# 10-RF_WIFI.net
KiCad netlist of a schematic drawn in Altium Designer
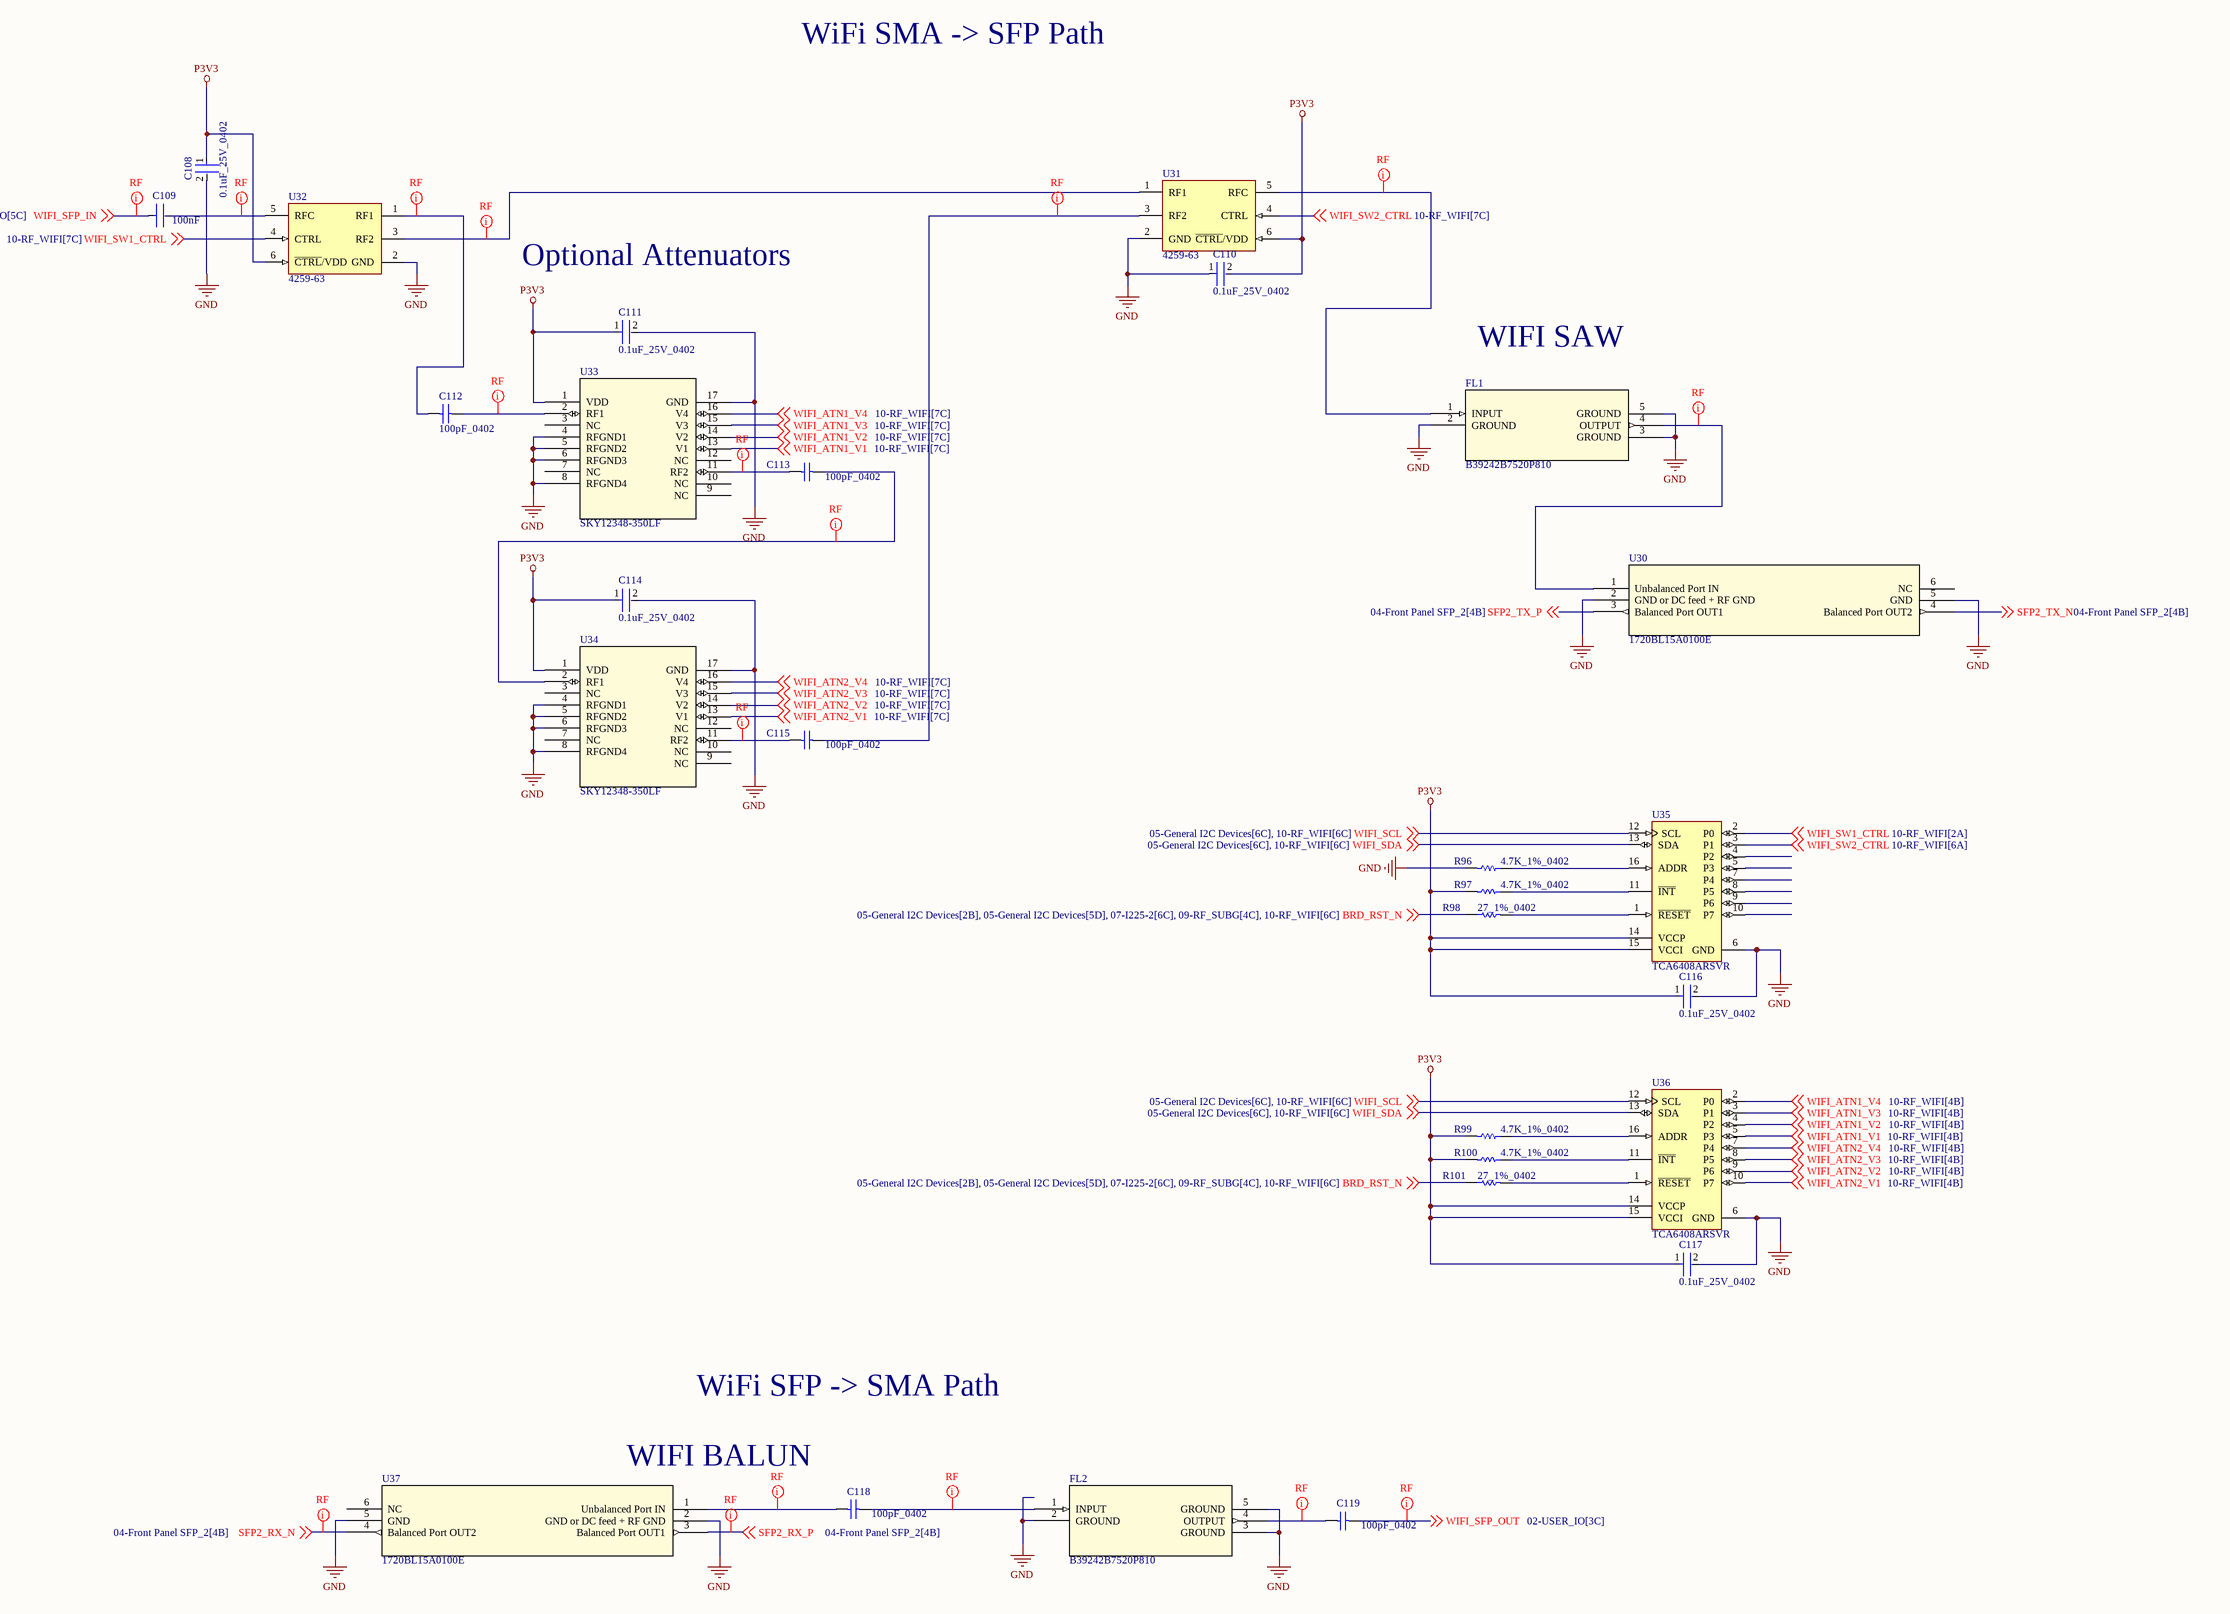
[diagram p0: 10-RF_WIFI.SchDoc]

(export (version "E")
  (design (tool "Eeschema 10.0.6"))
  (components
    (comp (ref "C108")
      (value "0.1uF_25V_0402")
      (footprint "FP-0402-L_1_0_1-W_0_5_0_1-IPC_C")
      (description "General Purpose Ceramic Capacitor, 0402, 100nF, 10%, X7R, 15%, 25V")
      (fields (field (name "VOLTAGE") "25V") (field (name "TOLERANCE") "10%"))
      (libsource (lib "Altium Content Vault") (part "b4654b650e69147ec39a6b967a45e02"))
    )
    (comp (ref "C109")
      (value "100nF")
      (footprint "FP-0402-L_1_0_0_05-W_0_5-IPC_B")
      (description "None")
      (fields (field (name "TOLERANCE") "10%"))
      (libsource (lib "") (part "b4654b650e69147ec39a6b967a45e02_1"))
    )
    (comp (ref "C110")
      (value "0.1uF_25V_0402")
      (footprint "FP-0402-L_1_0_1-W_0_5_0_1-IPC_C")
      (description "General Purpose Ceramic Capacitor, 0402, 100nF, 10%, X7R, 15%, 25V")
      (fields (field (name "VOLTAGE") "25V") (field (name "TOLERANCE") "10%"))
      (libsource (lib "Altium Content Vault") (part "b4654b650e69147ec39a6b967a45e02"))
    )
    (comp (ref "C111")
      (value "0.1uF_25V_0402")
      (footprint "FP-0402-L_1_0_1-W_0_5_0_1-IPC_C")
      (description "General Purpose Ceramic Capacitor, 0402, 100nF, 10%, X7R, 15%, 25V")
      (fields (field (name "VOLTAGE") "25V") (field (name "TOLERANCE") "10%"))
      (libsource (lib "Altium Content Vault") (part "b4654b650e69147ec39a6b967a45e02"))
    )
    (comp (ref "C112")
      (value "100pF_0402")
      (footprint "CAPC1005X55X25ML05T10")
      (fields (field (name "MANUFACTURER") "Murata") (field (name "PART NUMBER") "GRM1555C1H101JA01D"))
      (libsource (lib "Altium Content Vault") (part "CAP"))
    )
    (comp (ref "C113")
      (value "100pF_0402")
      (footprint "CAPC1005X55X25ML05T10")
      (fields (field (name "MANUFACTURER") "Murata") (field (name "PART NUMBER") "GRM1555C1H101JA01D"))
      (libsource (lib "Altium Content Vault") (part "CAP"))
    )
    (comp (ref "C114")
      (value "0.1uF_25V_0402")
      (footprint "FP-0402-L_1_0_1-W_0_5_0_1-IPC_C")
      (description "General Purpose Ceramic Capacitor, 0402, 100nF, 10%, X7R, 15%, 25V")
      (fields (field (name "VOLTAGE") "25V") (field (name "TOLERANCE") "10%"))
      (libsource (lib "Altium Content Vault") (part "b4654b650e69147ec39a6b967a45e02"))
    )
    (comp (ref "C115")
      (value "100pF_0402")
      (footprint "CAPC1005X55X25ML05T10")
      (fields (field (name "MANUFACTURER") "Murata") (field (name "PART NUMBER") "GRM1555C1H101JA01D"))
      (libsource (lib "Altium Content Vault") (part "CAP"))
    )
    (comp (ref "C116")
      (value "0.1uF_25V_0402")
      (footprint "FP-0402-L_1_0_1-W_0_5_0_1-IPC_C")
      (description "General Purpose Ceramic Capacitor, 0402, 100nF, 10%, X7R, 15%, 25V")
      (fields (field (name "VOLTAGE") "25V") (field (name "TOLERANCE") "10%"))
      (libsource (lib "Altium Content Vault") (part "b4654b650e69147ec39a6b967a45e02"))
    )
    (comp (ref "C117")
      (value "0.1uF_25V_0402")
      (footprint "FP-0402-L_1_0_1-W_0_5_0_1-IPC_C")
      (description "General Purpose Ceramic Capacitor, 0402, 100nF, 10%, X7R, 15%, 25V")
      (fields (field (name "VOLTAGE") "25V") (field (name "TOLERANCE") "10%"))
      (libsource (lib "Altium Content Vault") (part "b4654b650e69147ec39a6b967a45e02"))
    )
    (comp (ref "C118")
      (value "100pF_0402")
      (footprint "CAPC1005X55X25ML05T10")
      (fields (field (name "MANUFACTURER") "Murata") (field (name "PART NUMBER") "GRM1555C1H101JA01D"))
      (libsource (lib "Altium Content Vault") (part "CAP"))
    )
    (comp (ref "C119")
      (value "100pF_0402")
      (footprint "CAPC1005X55X25ML05T10")
      (fields (field (name "MANUFACTURER") "Murata") (field (name "PART NUMBER") "GRM1555C1H101JA01D"))
      (libsource (lib "Altium Content Vault") (part "CAP"))
    )
    (comp (ref "FL1")
      (value "B39242B7520P810")
      (footprint "SMD5_SAW-B7520_QUA")
      (description "No Description Available")
      (libsource (lib "B39242B7520P810") (part "B39242B7520P810"))
    )
    (comp (ref "FL2")
      (value "B39242B7520P810")
      (footprint "SMD5_SAW-B7520_QUA")
      (description "No Description Available")
      (libsource (lib "B39242B7520P810") (part "B39242B7520P810"))
    )
    (comp (ref "R96")
      (value "4.7K_1%_0402")
      (footprint "RESC1005X40X25NL10T10")
      (fields (field (name "MANUFACTURER") "Bourns") (field (name "PART NUMBER") "CR0402-FX-4701GLF"))
      (libsource (lib "Altium Content Vault") (part "RES"))
    )
    (comp (ref "R97")
      (value "4.7K_1%_0402")
      (footprint "RESC1005X40X25NL10T10")
      (fields (field (name "MANUFACTURER") "Bourns") (field (name "PART NUMBER") "CR0402-FX-4701GLF"))
      (libsource (lib "Altium Content Vault") (part "RES"))
    )
    (comp (ref "R98")
      (value "27_1%_0402")
      (footprint "RESC1005X40X25NL05T05")
      (fields (field (name "PART NUMBER") "CRCW040227R0FKED") (field (name "MANUFACTURER") "Vishay Dale"))
      (libsource (lib "Altium Content Vault") (part "RES"))
    )
    (comp (ref "R99")
      (value "4.7K_1%_0402")
      (footprint "RESC1005X40X25NL10T10")
      (fields (field (name "MANUFACTURER") "Bourns") (field (name "PART NUMBER") "CR0402-FX-4701GLF"))
      (libsource (lib "Altium Content Vault") (part "RES"))
    )
    (comp (ref "R100")
      (value "4.7K_1%_0402")
      (footprint "RESC1005X40X25NL10T10")
      (fields (field (name "MANUFACTURER") "Bourns") (field (name "PART NUMBER") "CR0402-FX-4701GLF"))
      (libsource (lib "Altium Content Vault") (part "RES"))
    )
    (comp (ref "R101")
      (value "27_1%_0402")
      (footprint "RESC1005X40X25NL05T05")
      (fields (field (name "PART NUMBER") "CRCW040227R0FKED") (field (name "MANUFACTURER") "Vishay Dale"))
      (libsource (lib "Altium Content Vault") (part "RES"))
    )
    (comp (ref "U30")
      (value "1720BL15A0100E")
      (footprint "SMT_15B0050E_JOT")
      (description "No Description Available")
      (libsource (lib "") (part "1720BL15A0100E_1"))
    )
    (comp (ref "U31")
      (value "4259-63")
      (footprint "PERE-SC-70-6_M")
      (description "IC RF Switch SPDT, 50 Ohm, 6-Pin SC70, RoHS, Tape and Reel")
      (fields (field (name "MANUFACTURER") "Peregrine Semiconductor"))
      (libsource (lib "") (part "PERE-PE4259-6_1"))
    )
    (comp (ref "U32")
      (value "4259-63")
      (footprint "PERE-SC-70-6_M")
      (description "IC RF Switch SPDT, 50 Ohm, 6-Pin SC70, RoHS, Tape and Reel")
      (fields (field (name "MANUFACTURER") "Peregrine Semiconductor"))
      (libsource (lib "Altium Content Vault") (part "PERE-PE4259-6"))
    )
    (comp (ref "U33")
      (value "SKY12348-350LF")
      (footprint "SKY12348-350LF_SKY")
      (description "No Description Available")
      (libsource (lib "SKY12348-350LF") (part "SKY12348-350LF"))
    )
    (comp (ref "U34")
      (value "SKY12348-350LF")
      (footprint "SKY12348-350LF_SKY")
      (description "No Description Available")
      (libsource (lib "SKY12348-350LF") (part "SKY12348-350LF"))
    )
    (comp (ref "U35")
      (value "TCA6408ARSVR")
      (footprint "RSV0016A_V")
      (fields (field (name "MANUFACTURER") "Texas Instruments"))
      (libsource (lib "Altium Content Vault") (part "TI-TCA6408A-UQFN_RSV-16"))
    )
    (comp (ref "U36")
      (value "TCA6408ARSVR")
      (footprint "RSV0016A_V")
      (fields (field (name "MANUFACTURER") "Texas Instruments"))
      (libsource (lib "Altium Content Vault") (part "TI-TCA6408A-UQFN_RSV-16"))
    )
    (comp (ref "U37")
      (value "1720BL15A0100E")
      (footprint "SMT_15B0050E_JOT")
      (description "No Description Available")
      (libsource (lib "1720BL15A0100E") (part "1720BL15A0100E"))
    )
  )
  (nets
    (net (code "1") (name "BRD_RST_N") (class "Default")
      (node (ref "R101") (pin "1") (pinfunction "1_1") (pintype "passive"))
      (node (ref "R98") (pin "1") (pinfunction "1_1") (pintype "passive"))
    )
    (net (code "2") (name "GND") (class "Default")
      (node (ref "C108") (pin "2") (pinfunction "2_2") (pintype "passive"))
      (node (ref "C110") (pin "1") (pinfunction "1_1") (pintype "passive"))
      (node (ref "C111") (pin "2") (pinfunction "2_2") (pintype "passive"))
      (node (ref "C114") (pin "2") (pinfunction "2_2") (pintype "passive"))
      (node (ref "C116") (pin "2") (pinfunction "2_2") (pintype "passive"))
      (node (ref "C117") (pin "2") (pinfunction "2_2") (pintype "passive"))
      (node (ref "FL1") (pin "2") (pinfunction "GROUND_2") (pintype "power_in"))
      (node (ref "FL1") (pin "3") (pinfunction "GROUND_3") (pintype "power_in"))
      (node (ref "FL1") (pin "5") (pinfunction "GROUND_5") (pintype "power_in"))
      (node (ref "FL2") (pin "2") (pinfunction "GROUND_2") (pintype "power_in"))
      (node (ref "FL2") (pin "3") (pinfunction "GROUND_3") (pintype "power_in"))
      (node (ref "FL2") (pin "5") (pinfunction "GROUND_5") (pintype "power_in"))
      (node (ref "R96") (pin "2") (pinfunction "2_2") (pintype "passive"))
      (node (ref "U30") (pin "2") (pinfunction "GND_or_DC_feed_+_RF_GND_2") (pintype "power_in"))
      (node (ref "U30") (pin "5") (pinfunction "GND_5") (pintype "power_in"))
      (node (ref "U31") (pin "2") (pinfunction "GND_2") (pintype "power_in"))
      (node (ref "U32") (pin "2") (pinfunction "GND_2") (pintype "power_in"))
      (node (ref "U33") (pin "17") (pinfunction "GND_17") (pintype "power_in"))
      (node (ref "U33") (pin "4") (pinfunction "RFGND1_4") (pintype "power_in"))
      (node (ref "U33") (pin "5") (pinfunction "RFGND2_5") (pintype "power_in"))
      (node (ref "U33") (pin "6") (pinfunction "RFGND3_6") (pintype "power_in"))
      (node (ref "U33") (pin "8") (pinfunction "RFGND4_8") (pintype "power_in"))
      (node (ref "U34") (pin "17") (pinfunction "GND_17") (pintype "power_in"))
      (node (ref "U34") (pin "4") (pinfunction "RFGND1_4") (pintype "power_in"))
      (node (ref "U34") (pin "5") (pinfunction "RFGND2_5") (pintype "power_in"))
      (node (ref "U34") (pin "6") (pinfunction "RFGND3_6") (pintype "power_in"))
      (node (ref "U34") (pin "8") (pinfunction "RFGND4_8") (pintype "power_in"))
      (node (ref "U35") (pin "6") (pinfunction "GND_6") (pintype "power_in"))
      (node (ref "U36") (pin "6") (pinfunction "GND_6") (pintype "power_in"))
      (node (ref "U37") (pin "2") (pinfunction "GND_or_DC_feed_+_RF_GND_2") (pintype "power_in"))
      (node (ref "U37") (pin "5") (pinfunction "GND_5") (pintype "power_in"))
    )
    (net (code "3") (name "Net-(FL1-INPUT)") (class "Default")
      (node (ref "FL1") (pin "1") (pinfunction "INPUT_1") (pintype "input"))
      (node (ref "U31") (pin "5") (pinfunction "RFC_5") (pintype "passive"))
    )
    (net (code "4") (name "Net-(FL1-OUTPUT)") (class "Default")
      (node (ref "FL1") (pin "4") (pinfunction "OUTPUT_4") (pintype "output"))
      (node (ref "U30") (pin "1") (pinfunction "Unbalanced_Port_IN_1") (pintype "passive"))
    )
    (net (code "5") (name "Net-(FL2-INPUT)") (class "Default")
      (node (ref "C118") (pin "2") (pinfunction "2_2") (pintype "passive"))
      (node (ref "FL2") (pin "1") (pinfunction "INPUT_1") (pintype "input"))
    )
    (net (code "6") (name "Net-(FL2-OUTPUT)") (class "Default")
      (node (ref "C119") (pin "1") (pinfunction "1_1") (pintype "passive"))
      (node (ref "FL2") (pin "4") (pinfunction "OUTPUT_4") (pintype "output"))
    )
    (net (code "7") (name "Net-(U31-RF1)") (class "Default")
      (node (ref "U31") (pin "1") (pinfunction "RF1_1") (pintype "passive"))
      (node (ref "U32") (pin "3") (pinfunction "RF2_3") (pintype "passive"))
    )
    (net (code "8") (name "Net-(U31-RF2)") (class "Default")
      (node (ref "C115") (pin "2") (pinfunction "2_2") (pintype "passive"))
      (node (ref "U31") (pin "3") (pinfunction "RF2_3") (pintype "passive"))
    )
    (net (code "9") (name "Net-(U32-RF1)") (class "Default")
      (node (ref "C112") (pin "1") (pinfunction "1_1") (pintype "passive"))
      (node (ref "U32") (pin "1") (pinfunction "RF1_1") (pintype "passive"))
    )
    (net (code "10") (name "Net-(U32-RFC)") (class "Default")
      (node (ref "C109") (pin "2") (pinfunction "2_2") (pintype "passive"))
      (node (ref "U32") (pin "5") (pinfunction "RFC_5") (pintype "passive"))
    )
    (net (code "11") (name "Net-(U33-RF1)") (class "Default")
      (node (ref "C112") (pin "2") (pinfunction "2_2") (pintype "passive"))
      (node (ref "U33") (pin "2") (pinfunction "RF1_2") (pintype "bidirectional"))
    )
    (net (code "12") (name "Net-(U33-RF2)") (class "Default")
      (node (ref "C113") (pin "1") (pinfunction "1_1") (pintype "passive"))
      (node (ref "U33") (pin "11") (pinfunction "RF2_11") (pintype "bidirectional"))
    )
    (net (code "13") (name "Net-(U34-RF1)") (class "Default")
      (node (ref "C113") (pin "2") (pinfunction "2_2") (pintype "passive"))
      (node (ref "U34") (pin "2") (pinfunction "RF1_2") (pintype "bidirectional"))
    )
    (net (code "14") (name "Net-(U34-RF2)") (class "Default")
      (node (ref "C115") (pin "1") (pinfunction "1_1") (pintype "passive"))
      (node (ref "U34") (pin "11") (pinfunction "RF2_11") (pintype "bidirectional"))
    )
    (net (code "15") (name "Net-(U35-ADDR)") (class "Default")
      (node (ref "R96") (pin "1") (pinfunction "1_1") (pintype "passive"))
      (node (ref "U35") (pin "16") (pinfunction "ADDR_16") (pintype "input"))
    )
    (net (code "16") (name "Net-(U35-~{INT})") (class "Default")
      (node (ref "R97") (pin "1") (pinfunction "1_1") (pintype "passive"))
      (node (ref "U35") (pin "11") (pinfunction "~{INT}_11") (pintype "open_collector"))
    )
    (net (code "17") (name "Net-(U35-~{RESET})") (class "Default")
      (node (ref "R98") (pin "2") (pinfunction "2_2") (pintype "passive"))
      (node (ref "U35") (pin "1") (pinfunction "~{RESET}_1") (pintype "input"))
    )
    (net (code "18") (name "Net-(U36-ADDR)") (class "Default")
      (node (ref "R99") (pin "1") (pinfunction "1_1") (pintype "passive"))
      (node (ref "U36") (pin "16") (pinfunction "ADDR_16") (pintype "input"))
    )
    (net (code "19") (name "Net-(U36-~{INT})") (class "Default")
      (node (ref "R100") (pin "1") (pinfunction "1_1") (pintype "passive"))
      (node (ref "U36") (pin "11") (pinfunction "~{INT}_11") (pintype "open_collector"))
    )
    (net (code "20") (name "Net-(U36-~{RESET})") (class "Default")
      (node (ref "R101") (pin "2") (pinfunction "2_2") (pintype "passive"))
      (node (ref "U36") (pin "1") (pinfunction "~{RESET}_1") (pintype "input"))
    )
    (net (code "21") (name "Net-(U37-Unbalanced_Port_IN)") (class "Default")
      (node (ref "C118") (pin "1") (pinfunction "1_1") (pintype "passive"))
      (node (ref "U37") (pin "1") (pinfunction "Unbalanced_Port_IN_1") (pintype "passive"))
    )
    (net (code "22") (name "P3V3") (class "Default")
      (node (ref "C108") (pin "1") (pinfunction "1_1") (pintype "passive"))
      (node (ref "C110") (pin "2") (pinfunction "2_2") (pintype "passive"))
      (node (ref "C111") (pin "1") (pinfunction "1_1") (pintype "passive"))
      (node (ref "C114") (pin "1") (pinfunction "1_1") (pintype "passive"))
      (node (ref "C116") (pin "1") (pinfunction "1_1") (pintype "passive"))
      (node (ref "C117") (pin "1") (pinfunction "1_1") (pintype "passive"))
      (node (ref "R100") (pin "2") (pinfunction "2_2") (pintype "passive"))
      (node (ref "R97") (pin "2") (pinfunction "2_2") (pintype "passive"))
      (node (ref "R99") (pin "2") (pinfunction "2_2") (pintype "passive"))
      (node (ref "U31") (pin "6") (pinfunction "~{CTRL}/VDD_6") (pintype "input"))
      (node (ref "U32") (pin "6") (pinfunction "~{CTRL}/VDD_6") (pintype "input"))
      (node (ref "U33") (pin "1") (pinfunction "VDD_1") (pintype "power_in"))
      (node (ref "U34") (pin "1") (pinfunction "VDD_1") (pintype "power_in"))
      (node (ref "U35") (pin "14") (pinfunction "VCCP_14") (pintype "power_in"))
      (node (ref "U35") (pin "15") (pinfunction "VCCI_15") (pintype "power_in"))
      (node (ref "U36") (pin "14") (pinfunction "VCCP_14") (pintype "power_in"))
      (node (ref "U36") (pin "15") (pinfunction "VCCI_15") (pintype "power_in"))
    )
    (net (code "23") (name "SFP2_RX_N") (class "Default")
      (node (ref "U37") (pin "4") (pinfunction "Balanced_Port_OUT2_4") (pintype "output"))
    )
    (net (code "24") (name "SFP2_RX_P") (class "Default")
      (node (ref "U37") (pin "3") (pinfunction "Balanced_Port_OUT1_3") (pintype "output"))
    )
    (net (code "25") (name "SFP2_TX_N") (class "Default")
      (node (ref "U30") (pin "4") (pinfunction "Balanced_Port_OUT2_4") (pintype "output"))
    )
    (net (code "26") (name "SFP2_TX_P") (class "Default")
      (node (ref "U30") (pin "3") (pinfunction "Balanced_Port_OUT1_3") (pintype "output"))
    )
    (net (code "27") (name "WIFI_ATN1_V1") (class "Default")
      (node (ref "U33") (pin "13") (pinfunction "V1_13") (pintype "bidirectional"))
      (node (ref "U36") (pin "5") (pinfunction "P3_5") (pintype "bidirectional"))
    )
    (net (code "28") (name "WIFI_ATN1_V2") (class "Default")
      (node (ref "U33") (pin "14") (pinfunction "V2_14") (pintype "bidirectional"))
      (node (ref "U36") (pin "4") (pinfunction "P2_4") (pintype "bidirectional"))
    )
    (net (code "29") (name "WIFI_ATN1_V3") (class "Default")
      (node (ref "U33") (pin "15") (pinfunction "V3_15") (pintype "bidirectional"))
      (node (ref "U36") (pin "3") (pinfunction "P1_3") (pintype "bidirectional"))
    )
    (net (code "30") (name "WIFI_ATN1_V4") (class "Default")
      (node (ref "U33") (pin "16") (pinfunction "V4_16") (pintype "bidirectional"))
      (node (ref "U36") (pin "2") (pinfunction "P0_2") (pintype "bidirectional"))
    )
    (net (code "31") (name "WIFI_ATN2_V1") (class "Default")
      (node (ref "U34") (pin "13") (pinfunction "V1_13") (pintype "bidirectional"))
      (node (ref "U36") (pin "10") (pinfunction "P7_10") (pintype "bidirectional"))
    )
    (net (code "32") (name "WIFI_ATN2_V2") (class "Default")
      (node (ref "U34") (pin "14") (pinfunction "V2_14") (pintype "bidirectional"))
      (node (ref "U36") (pin "9") (pinfunction "P6_9") (pintype "bidirectional"))
    )
    (net (code "33") (name "WIFI_ATN2_V3") (class "Default")
      (node (ref "U34") (pin "15") (pinfunction "V3_15") (pintype "bidirectional"))
      (node (ref "U36") (pin "8") (pinfunction "P5_8") (pintype "bidirectional"))
    )
    (net (code "34") (name "WIFI_ATN2_V4") (class "Default")
      (node (ref "U34") (pin "16") (pinfunction "V4_16") (pintype "bidirectional"))
      (node (ref "U36") (pin "7") (pinfunction "P4_7") (pintype "bidirectional"))
    )
    (net (code "35") (name "WIFI_SCL") (class "Default")
      (node (ref "U35") (pin "12") (pinfunction "SCL_12") (pintype "input"))
      (node (ref "U36") (pin "12") (pinfunction "SCL_12") (pintype "input"))
    )
    (net (code "36") (name "WIFI_SDA") (class "Default")
      (node (ref "U35") (pin "13") (pinfunction "SDA_13") (pintype "bidirectional"))
      (node (ref "U36") (pin "13") (pinfunction "SDA_13") (pintype "bidirectional"))
    )
    (net (code "37") (name "WIFI_SFP_IN") (class "Default")
      (node (ref "C109") (pin "1") (pinfunction "1_1") (pintype "passive"))
    )
    (net (code "38") (name "WIFI_SFP_OUT") (class "Default")
      (node (ref "C119") (pin "2") (pinfunction "2_2") (pintype "passive"))
    )
    (net (code "39") (name "WIFI_SW1_CTRL") (class "Default")
      (node (ref "U32") (pin "4") (pinfunction "CTRL_4") (pintype "input"))
      (node (ref "U35") (pin "2") (pinfunction "P0_2") (pintype "bidirectional"))
    )
    (net (code "40") (name "WIFI_SW2_CTRL") (class "Default")
      (node (ref "U31") (pin "4") (pinfunction "CTRL_4") (pintype "input"))
      (node (ref "U35") (pin "3") (pinfunction "P1_3") (pintype "bidirectional"))
    )
    (net (code "41") (name "unconnected-(U30-NC-Pad6)") (class "Default")
      (node (ref "U30") (pin "6") (pinfunction "NC_6") (pintype "passive"))
    )
    (net (code "42") (name "unconnected-(U33-NC-Pad3)") (class "Default")
      (node (ref "U33") (pin "3") (pinfunction "NC_3") (pintype "passive"))
    )
    (net (code "43") (name "unconnected-(U33-NC-Pad7)") (class "Default")
      (node (ref "U33") (pin "7") (pinfunction "NC_7") (pintype "passive"))
    )
    (net (code "44") (name "unconnected-(U33-NC-Pad9)") (class "Default")
      (node (ref "U33") (pin "9") (pinfunction "NC_9") (pintype "passive"))
    )
    (net (code "45") (name "unconnected-(U33-NC-Pad10)") (class "Default")
      (node (ref "U33") (pin "10") (pinfunction "NC_10") (pintype "passive"))
    )
    (net (code "46") (name "unconnected-(U33-NC-Pad12)") (class "Default")
      (node (ref "U33") (pin "12") (pinfunction "NC_12") (pintype "passive"))
    )
    (net (code "47") (name "unconnected-(U34-NC-Pad3)") (class "Default")
      (node (ref "U34") (pin "3") (pinfunction "NC_3") (pintype "passive"))
    )
    (net (code "48") (name "unconnected-(U34-NC-Pad7)") (class "Default")
      (node (ref "U34") (pin "7") (pinfunction "NC_7") (pintype "passive"))
    )
    (net (code "49") (name "unconnected-(U34-NC-Pad9)") (class "Default")
      (node (ref "U34") (pin "9") (pinfunction "NC_9") (pintype "passive"))
    )
    (net (code "50") (name "unconnected-(U34-NC-Pad10)") (class "Default")
      (node (ref "U34") (pin "10") (pinfunction "NC_10") (pintype "passive"))
    )
    (net (code "51") (name "unconnected-(U34-NC-Pad12)") (class "Default")
      (node (ref "U34") (pin "12") (pinfunction "NC_12") (pintype "passive"))
    )
    (net (code "52") (name "unconnected-(U35-P2-Pad4)") (class "Default")
      (node (ref "U35") (pin "4") (pinfunction "P2_4") (pintype "bidirectional"))
    )
    (net (code "53") (name "unconnected-(U35-P3-Pad5)") (class "Default")
      (node (ref "U35") (pin "5") (pinfunction "P3_5") (pintype "bidirectional"))
    )
    (net (code "54") (name "unconnected-(U35-P4-Pad7)") (class "Default")
      (node (ref "U35") (pin "7") (pinfunction "P4_7") (pintype "bidirectional"))
    )
    (net (code "55") (name "unconnected-(U35-P5-Pad8)") (class "Default")
      (node (ref "U35") (pin "8") (pinfunction "P5_8") (pintype "bidirectional"))
    )
    (net (code "56") (name "unconnected-(U35-P6-Pad9)") (class "Default")
      (node (ref "U35") (pin "9") (pinfunction "P6_9") (pintype "bidirectional"))
    )
    (net (code "57") (name "unconnected-(U35-P7-Pad10)") (class "Default")
      (node (ref "U35") (pin "10") (pinfunction "P7_10") (pintype "bidirectional"))
    )
    (net (code "58") (name "unconnected-(U37-NC-Pad6)") (class "Default")
      (node (ref "U37") (pin "6") (pinfunction "NC_6") (pintype "passive"))
    )
  )
)
